# mjoy_v2.net
KiCad netlist of a schematic drawn in EAGLE
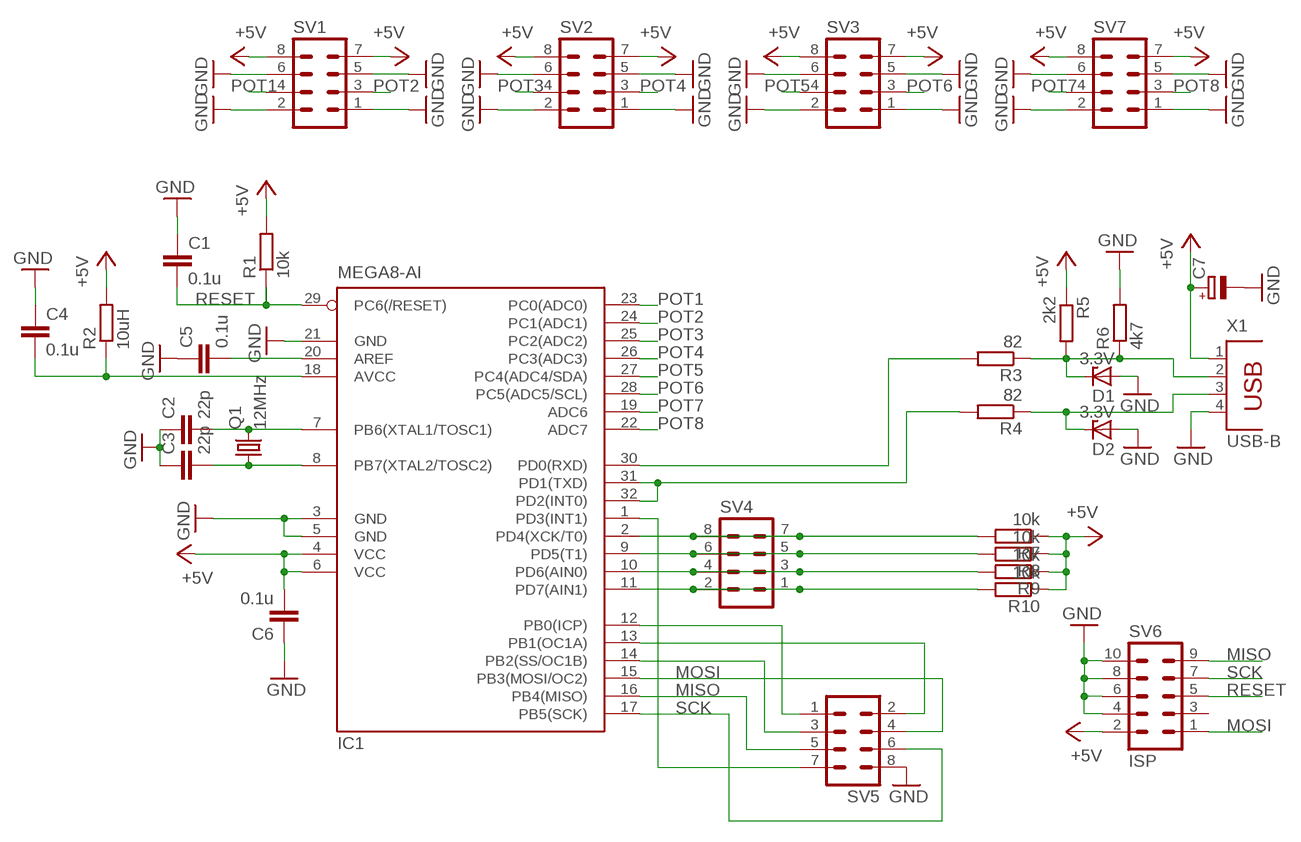
[diagram p0: schematic, sheet 1]

(export (version "E")
  (design (tool "Eeschema 10.0.6"))
  (components
    (comp (ref "C1")
      (value "0.1u")
      (footprint "eagle-import:C0805")
      (libsource (lib "eagle-import") (part "C-EUC0805"))
    )
    (comp (ref "C2")
      (value "22p")
      (footprint "eagle-import:C0805")
      (libsource (lib "eagle-import") (part "C-EUC0805"))
    )
    (comp (ref "C3")
      (value "22p")
      (footprint "eagle-import:C0805")
      (libsource (lib "eagle-import") (part "C-EUC0805"))
    )
    (comp (ref "C4")
      (value "0.1u")
      (footprint "eagle-import:C0805")
      (libsource (lib "eagle-import") (part "C-EUC0805"))
    )
    (comp (ref "C5")
      (value "0.1u")
      (footprint "eagle-import:C0805")
      (libsource (lib "eagle-import") (part "C-EUC0805"))
    )
    (comp (ref "C6")
      (value "0.1u")
      (footprint "eagle-import:C0805")
      (libsource (lib "eagle-import") (part "C-EUC0805"))
    )
    (comp (ref "C7")
      (value "CPOL-EUSMCD")
      (footprint "eagle-import:SMC_D")
      (libsource (lib "eagle-import") (part "CPOL-EUSMCD"))
    )
    (comp (ref "D1")
      (value "3.3V")
      (footprint "eagle-import:SOD80C")
      (libsource (lib "eagle-import") (part "ZENER-DIODESOD80C"))
    )
    (comp (ref "D2")
      (value "3.3V")
      (footprint "eagle-import:SOD80C")
      (libsource (lib "eagle-import") (part "ZENER-DIODESOD80C"))
    )
    (comp (ref "IC1")
      (value "MEGA8-AI")
      (footprint "eagle-import:TQFP32-08")
      (libsource (lib "eagle-import") (part "MEGA8-AI"))
    )
    (comp (ref "Q1")
      (value "12MHz")
      (footprint "eagle-import:HC49UP")
      (libsource (lib "eagle-import") (part "CRYSTALHC49UP"))
    )
    (comp (ref "R1")
      (value "10k")
      (footprint "eagle-import:R0805")
      (libsource (lib "eagle-import") (part "R-EU_R0805"))
    )
    (comp (ref "R2")
      (value "10uH")
      (footprint "eagle-import:R1210")
      (libsource (lib "eagle-import") (part "R-EU_R1210"))
    )
    (comp (ref "R3")
      (value "82")
      (footprint "eagle-import:R0805")
      (libsource (lib "eagle-import") (part "R-EU_R0805"))
    )
    (comp (ref "R4")
      (value "82")
      (footprint "eagle-import:R0805")
      (libsource (lib "eagle-import") (part "R-EU_R0805"))
    )
    (comp (ref "R5")
      (value "2k2")
      (footprint "eagle-import:R0805")
      (libsource (lib "eagle-import") (part "R-EU_R0805"))
    )
    (comp (ref "R6")
      (value "4k7")
      (footprint "eagle-import:R0805")
      (libsource (lib "eagle-import") (part "R-EU_R0805"))
    )
    (comp (ref "R7")
      (value "10k")
      (footprint "eagle-import:R0805")
      (libsource (lib "eagle-import") (part "R-EU_R0805"))
    )
    (comp (ref "R8")
      (value "10k")
      (footprint "eagle-import:R0805")
      (libsource (lib "eagle-import") (part "R-EU_R0805"))
    )
    (comp (ref "R9")
      (value "10k")
      (footprint "eagle-import:R0805")
      (libsource (lib "eagle-import") (part "R-EU_R0805"))
    )
    (comp (ref "R10")
      (value "10k")
      (footprint "eagle-import:R0805")
      (libsource (lib "eagle-import") (part "R-EU_R0805"))
    )
    (comp (ref "SV1")
      (value "MA04-2")
      (footprint "eagle-import:MA04-2")
      (libsource (lib "eagle-import") (part "MA04-2"))
    )
    (comp (ref "SV2")
      (value "MA04-2")
      (footprint "eagle-import:MA04-2")
      (libsource (lib "eagle-import") (part "MA04-2"))
    )
    (comp (ref "SV3")
      (value "MA04-2")
      (footprint "eagle-import:MA04-2")
      (libsource (lib "eagle-import") (part "MA04-2"))
    )
    (comp (ref "SV4")
      (value "MA04-2")
      (footprint "eagle-import:MA04-2")
      (libsource (lib "eagle-import") (part "MA04-2"))
    )
    (comp (ref "SV5")
      (value "MA04-2")
      (footprint "eagle-import:MA04-2")
      (libsource (lib "eagle-import") (part "MA04-2"))
    )
    (comp (ref "SV6")
      (value "ISP")
      (footprint "eagle-import:MA05-2")
      (libsource (lib "eagle-import") (part "MA05-2"))
    )
    (comp (ref "SV7")
      (value "MA04-2")
      (footprint "eagle-import:MA04-2")
      (libsource (lib "eagle-import") (part "MA04-2"))
    )
    (comp (ref "X1")
      (value "USB-B")
      (footprint "eagle-import:PN61729")
      (libsource (lib "eagle-import") (part "PN61729"))
    )
  )
  (nets
    (net (code "1") (name "+5V") (class "Default")
      (node (ref "C6") (pin "2") (pinfunction "2_2") (pintype "passive"))
      (node (ref "C7") (pin "+") (pinfunction "+_+") (pintype "passive"))
      (node (ref "IC1") (pin "4") (pinfunction "VCC_4") (pintype "power_in"))
      (node (ref "IC1") (pin "6") (pinfunction "VCC_6") (pintype "power_in"))
      (node (ref "R1") (pin "2") (pinfunction "2_2") (pintype "passive"))
      (node (ref "R10") (pin "1") (pinfunction "1_1") (pintype "passive"))
      (node (ref "R2") (pin "2") (pinfunction "2_2") (pintype "passive"))
      (node (ref "R5") (pin "1") (pinfunction "1_1") (pintype "passive"))
      (node (ref "R7") (pin "1") (pinfunction "1_1") (pintype "passive"))
      (node (ref "R8") (pin "1") (pinfunction "1_1") (pintype "passive"))
      (node (ref "R9") (pin "1") (pinfunction "1_1") (pintype "passive"))
      (node (ref "SV1") (pin "7") (pinfunction "7_7") (pintype "passive"))
      (node (ref "SV1") (pin "8") (pinfunction "8_8") (pintype "passive"))
      (node (ref "SV2") (pin "7") (pinfunction "7_7") (pintype "passive"))
      (node (ref "SV2") (pin "8") (pinfunction "8_8") (pintype "passive"))
      (node (ref "SV3") (pin "7") (pinfunction "7_7") (pintype "passive"))
      (node (ref "SV3") (pin "8") (pinfunction "8_8") (pintype "passive"))
      (node (ref "SV6") (pin "2") (pinfunction "2_2") (pintype "passive"))
      (node (ref "SV7") (pin "7") (pinfunction "7_7") (pintype "passive"))
      (node (ref "SV7") (pin "8") (pinfunction "8_8") (pintype "passive"))
      (node (ref "X1") (pin "1") (pinfunction "1_1") (pintype "passive"))
    )
    (net (code "2") (name "/MISO") (class "Default")
      (node (ref "IC1") (pin "16") (pinfunction "PB4(MISO)_16") (pintype "bidirectional"))
      (node (ref "SV5") (pin "5") (pinfunction "5_5") (pintype "passive"))
      (node (ref "SV6") (pin "9") (pinfunction "9_9") (pintype "passive"))
    )
    (net (code "3") (name "/MOSI") (class "Default")
      (node (ref "IC1") (pin "15") (pinfunction "PB3(MOSI/OC2)_15") (pintype "bidirectional"))
      (node (ref "SV5") (pin "4") (pinfunction "4_4") (pintype "passive"))
      (node (ref "SV6") (pin "1") (pinfunction "1_1") (pintype "passive"))
    )
    (net (code "4") (name "/POT1") (class "Default")
      (node (ref "IC1") (pin "23") (pinfunction "PC0(ADC0)_23") (pintype "bidirectional"))
      (node (ref "SV1") (pin "4") (pinfunction "4_4") (pintype "passive"))
    )
    (net (code "5") (name "/POT2") (class "Default")
      (node (ref "IC1") (pin "24") (pinfunction "PC1(ADC1)_24") (pintype "bidirectional"))
      (node (ref "SV1") (pin "3") (pinfunction "3_3") (pintype "passive"))
    )
    (net (code "6") (name "/POT3") (class "Default")
      (node (ref "IC1") (pin "25") (pinfunction "PC2(ADC2)_25") (pintype "bidirectional"))
      (node (ref "SV2") (pin "4") (pinfunction "4_4") (pintype "passive"))
    )
    (net (code "7") (name "/POT4") (class "Default")
      (node (ref "IC1") (pin "26") (pinfunction "PC3(ADC3)_26") (pintype "bidirectional"))
      (node (ref "SV2") (pin "3") (pinfunction "3_3") (pintype "passive"))
    )
    (net (code "8") (name "/POT5") (class "Default")
      (node (ref "IC1") (pin "27") (pinfunction "PC4(ADC4/SDA)_27") (pintype "bidirectional"))
      (node (ref "SV3") (pin "4") (pinfunction "4_4") (pintype "passive"))
    )
    (net (code "9") (name "/POT6") (class "Default")
      (node (ref "IC1") (pin "28") (pinfunction "PC5(ADC5/SCL)_28") (pintype "bidirectional"))
      (node (ref "SV3") (pin "3") (pinfunction "3_3") (pintype "passive"))
    )
    (net (code "10") (name "/POT7") (class "Default")
      (node (ref "IC1") (pin "19") (pinfunction "ADC6_19") (pintype "bidirectional"))
      (node (ref "SV7") (pin "4") (pinfunction "4_4") (pintype "passive"))
    )
    (net (code "11") (name "/POT8") (class "Default")
      (node (ref "IC1") (pin "22") (pinfunction "ADC7_22") (pintype "bidirectional"))
      (node (ref "SV7") (pin "3") (pinfunction "3_3") (pintype "passive"))
    )
    (net (code "12") (name "/RESET") (class "Default")
      (node (ref "C1") (pin "2") (pinfunction "2_2") (pintype "passive"))
      (node (ref "IC1") (pin "29") (pinfunction "PC6(/RESET)_29") (pintype "bidirectional"))
      (node (ref "R1") (pin "1") (pinfunction "1_1") (pintype "passive"))
      (node (ref "SV6") (pin "5") (pinfunction "5_5") (pintype "passive"))
    )
    (net (code "13") (name "/SCK") (class "Default")
      (node (ref "IC1") (pin "17") (pinfunction "PB5(SCK)_17") (pintype "bidirectional"))
      (node (ref "SV5") (pin "6") (pinfunction "6_6") (pintype "passive"))
      (node (ref "SV6") (pin "7") (pinfunction "7_7") (pintype "passive"))
    )
    (net (code "14") (name "GND") (class "Default")
      (node (ref "C1") (pin "1") (pinfunction "1_1") (pintype "passive"))
      (node (ref "C2") (pin "1") (pinfunction "1_1") (pintype "passive"))
      (node (ref "C3") (pin "1") (pinfunction "1_1") (pintype "passive"))
      (node (ref "C4") (pin "1") (pinfunction "1_1") (pintype "passive"))
      (node (ref "C5") (pin "1") (pinfunction "1_1") (pintype "passive"))
      (node (ref "C6") (pin "1") (pinfunction "1_1") (pintype "passive"))
      (node (ref "C7") (pin "-") (pinfunction "-_-") (pintype "passive"))
      (node (ref "D1") (pin "A") (pinfunction "A_A") (pintype "passive"))
      (node (ref "D2") (pin "A") (pinfunction "A_A") (pintype "passive"))
      (node (ref "IC1") (pin "21") (pinfunction "GND_21") (pintype "power_in"))
      (node (ref "IC1") (pin "3") (pinfunction "GND_3") (pintype "power_in"))
      (node (ref "IC1") (pin "5") (pinfunction "GND_5") (pintype "power_in"))
      (node (ref "R6") (pin "2") (pinfunction "2_2") (pintype "passive"))
      (node (ref "SV1") (pin "1") (pinfunction "1_1") (pintype "passive"))
      (node (ref "SV1") (pin "2") (pinfunction "2_2") (pintype "passive"))
      (node (ref "SV1") (pin "5") (pinfunction "5_5") (pintype "passive"))
      (node (ref "SV1") (pin "6") (pinfunction "6_6") (pintype "passive"))
      (node (ref "SV2") (pin "1") (pinfunction "1_1") (pintype "passive"))
      (node (ref "SV2") (pin "2") (pinfunction "2_2") (pintype "passive"))
      (node (ref "SV2") (pin "5") (pinfunction "5_5") (pintype "passive"))
      (node (ref "SV2") (pin "6") (pinfunction "6_6") (pintype "passive"))
      (node (ref "SV3") (pin "1") (pinfunction "1_1") (pintype "passive"))
      (node (ref "SV3") (pin "2") (pinfunction "2_2") (pintype "passive"))
      (node (ref "SV3") (pin "5") (pinfunction "5_5") (pintype "passive"))
      (node (ref "SV3") (pin "6") (pinfunction "6_6") (pintype "passive"))
      (node (ref "SV5") (pin "8") (pinfunction "8_8") (pintype "passive"))
      (node (ref "SV6") (pin "10") (pinfunction "10_10") (pintype "passive"))
      (node (ref "SV6") (pin "4") (pinfunction "4_4") (pintype "passive"))
      (node (ref "SV6") (pin "6") (pinfunction "6_6") (pintype "passive"))
      (node (ref "SV6") (pin "8") (pinfunction "8_8") (pintype "passive"))
      (node (ref "SV7") (pin "1") (pinfunction "1_1") (pintype "passive"))
      (node (ref "SV7") (pin "2") (pinfunction "2_2") (pintype "passive"))
      (node (ref "SV7") (pin "5") (pinfunction "5_5") (pintype "passive"))
      (node (ref "SV7") (pin "6") (pinfunction "6_6") (pintype "passive"))
      (node (ref "X1") (pin "4") (pinfunction "4_4") (pintype "passive"))
    )
    (net (code "15") (name "Net-(D1-PadC)") (class "Default")
      (node (ref "D1") (pin "C") (pinfunction "C_C") (pintype "passive"))
      (node (ref "R3") (pin "1") (pinfunction "1_1") (pintype "passive"))
      (node (ref "R5") (pin "2") (pinfunction "2_2") (pintype "passive"))
      (node (ref "R6") (pin "1") (pinfunction "1_1") (pintype "passive"))
      (node (ref "X1") (pin "2") (pinfunction "2_2") (pintype "passive"))
    )
    (net (code "16") (name "Net-(D2-PadC)") (class "Default")
      (node (ref "D2") (pin "C") (pinfunction "C_C") (pintype "passive"))
      (node (ref "R4") (pin "1") (pinfunction "1_1") (pintype "passive"))
      (node (ref "X1") (pin "3") (pinfunction "3_3") (pintype "passive"))
    )
    (net (code "17") (name "Net-(IC1-AREF)") (class "Default")
      (node (ref "C5") (pin "2") (pinfunction "2_2") (pintype "passive"))
      (node (ref "IC1") (pin "20") (pinfunction "AREF_20") (pintype "passive"))
    )
    (net (code "18") (name "Net-(IC1-AVCC)") (class "Default")
      (node (ref "C4") (pin "2") (pinfunction "2_2") (pintype "passive"))
      (node (ref "IC1") (pin "18") (pinfunction "AVCC_18") (pintype "power_in"))
      (node (ref "R2") (pin "1") (pinfunction "1_1") (pintype "passive"))
    )
    (net (code "19") (name "Net-(IC1-PB0(ICP))") (class "Default")
      (node (ref "IC1") (pin "12") (pinfunction "PB0(ICP)_12") (pintype "bidirectional"))
      (node (ref "SV5") (pin "1") (pinfunction "1_1") (pintype "passive"))
    )
    (net (code "20") (name "Net-(IC1-PB1(OC1A))") (class "Default")
      (node (ref "IC1") (pin "13") (pinfunction "PB1(OC1A)_13") (pintype "bidirectional"))
      (node (ref "SV5") (pin "2") (pinfunction "2_2") (pintype "passive"))
    )
    (net (code "21") (name "Net-(IC1-PB2(SS{slash}OC1B))") (class "Default")
      (node (ref "IC1") (pin "14") (pinfunction "PB2(SS/OC1B)_14") (pintype "bidirectional"))
      (node (ref "SV5") (pin "3") (pinfunction "3_3") (pintype "passive"))
    )
    (net (code "22") (name "Net-(IC1-PB6(XTAL1{slash}TOSC1))") (class "Default")
      (node (ref "C2") (pin "2") (pinfunction "2_2") (pintype "passive"))
      (node (ref "IC1") (pin "7") (pinfunction "PB6(XTAL1/TOSC1)_7") (pintype "bidirectional"))
      (node (ref "Q1") (pin "2") (pinfunction "2_2") (pintype "passive"))
    )
    (net (code "23") (name "Net-(IC1-PB7(XTAL2{slash}TOSC2))") (class "Default")
      (node (ref "C3") (pin "2") (pinfunction "2_2") (pintype "passive"))
      (node (ref "IC1") (pin "8") (pinfunction "PB7(XTAL2/TOSC2)_8") (pintype "bidirectional"))
      (node (ref "Q1") (pin "1") (pinfunction "1_1") (pintype "passive"))
    )
    (net (code "24") (name "Net-(IC1-PD0(RXD))") (class "Default")
      (node (ref "IC1") (pin "30") (pinfunction "PD0(RXD)_30") (pintype "bidirectional"))
      (node (ref "R3") (pin "2") (pinfunction "2_2") (pintype "passive"))
    )
    (net (code "25") (name "Net-(IC1-PD1(TXD))") (class "Default")
      (node (ref "IC1") (pin "31") (pinfunction "PD1(TXD)_31") (pintype "bidirectional"))
      (node (ref "IC1") (pin "32") (pinfunction "PD2(INT0)_32") (pintype "bidirectional"))
      (node (ref "R4") (pin "2") (pinfunction "2_2") (pintype "passive"))
    )
    (net (code "26") (name "Net-(IC1-PD3(INT1))") (class "Default")
      (node (ref "IC1") (pin "1") (pinfunction "PD3(INT1)_1") (pintype "bidirectional"))
      (node (ref "SV5") (pin "7") (pinfunction "7_7") (pintype "passive"))
    )
    (net (code "27") (name "Net-(IC1-PD4(XCK{slash}T0))") (class "Default")
      (node (ref "IC1") (pin "2") (pinfunction "PD4(XCK/T0)_2") (pintype "bidirectional"))
      (node (ref "R7") (pin "2") (pinfunction "2_2") (pintype "passive"))
      (node (ref "SV4") (pin "7") (pinfunction "7_7") (pintype "passive"))
      (node (ref "SV4") (pin "8") (pinfunction "8_8") (pintype "passive"))
    )
    (net (code "28") (name "Net-(IC1-PD5(T1))") (class "Default")
      (node (ref "IC1") (pin "9") (pinfunction "PD5(T1)_9") (pintype "bidirectional"))
      (node (ref "R8") (pin "2") (pinfunction "2_2") (pintype "passive"))
      (node (ref "SV4") (pin "5") (pinfunction "5_5") (pintype "passive"))
      (node (ref "SV4") (pin "6") (pinfunction "6_6") (pintype "passive"))
    )
    (net (code "29") (name "Net-(IC1-PD6(AIN0))") (class "Default")
      (node (ref "IC1") (pin "10") (pinfunction "PD6(AIN0)_10") (pintype "bidirectional"))
      (node (ref "R9") (pin "2") (pinfunction "2_2") (pintype "passive"))
      (node (ref "SV4") (pin "3") (pinfunction "3_3") (pintype "passive"))
      (node (ref "SV4") (pin "4") (pinfunction "4_4") (pintype "passive"))
    )
    (net (code "30") (name "Net-(IC1-PD7(AIN1))") (class "Default")
      (node (ref "IC1") (pin "11") (pinfunction "PD7(AIN1)_11") (pintype "bidirectional"))
      (node (ref "R10") (pin "2") (pinfunction "2_2") (pintype "passive"))
      (node (ref "SV4") (pin "1") (pinfunction "1_1") (pintype "passive"))
      (node (ref "SV4") (pin "2") (pinfunction "2_2") (pintype "passive"))
    )
    (net (code "31") (name "unconnected-(SV6-Pad3)") (class "Default")
      (node (ref "SV6") (pin "3") (pinfunction "3_3") (pintype "passive"))
    )
  )
)
